# ECE411.net
KiCad netlist of a schematic drawn in EAGLE
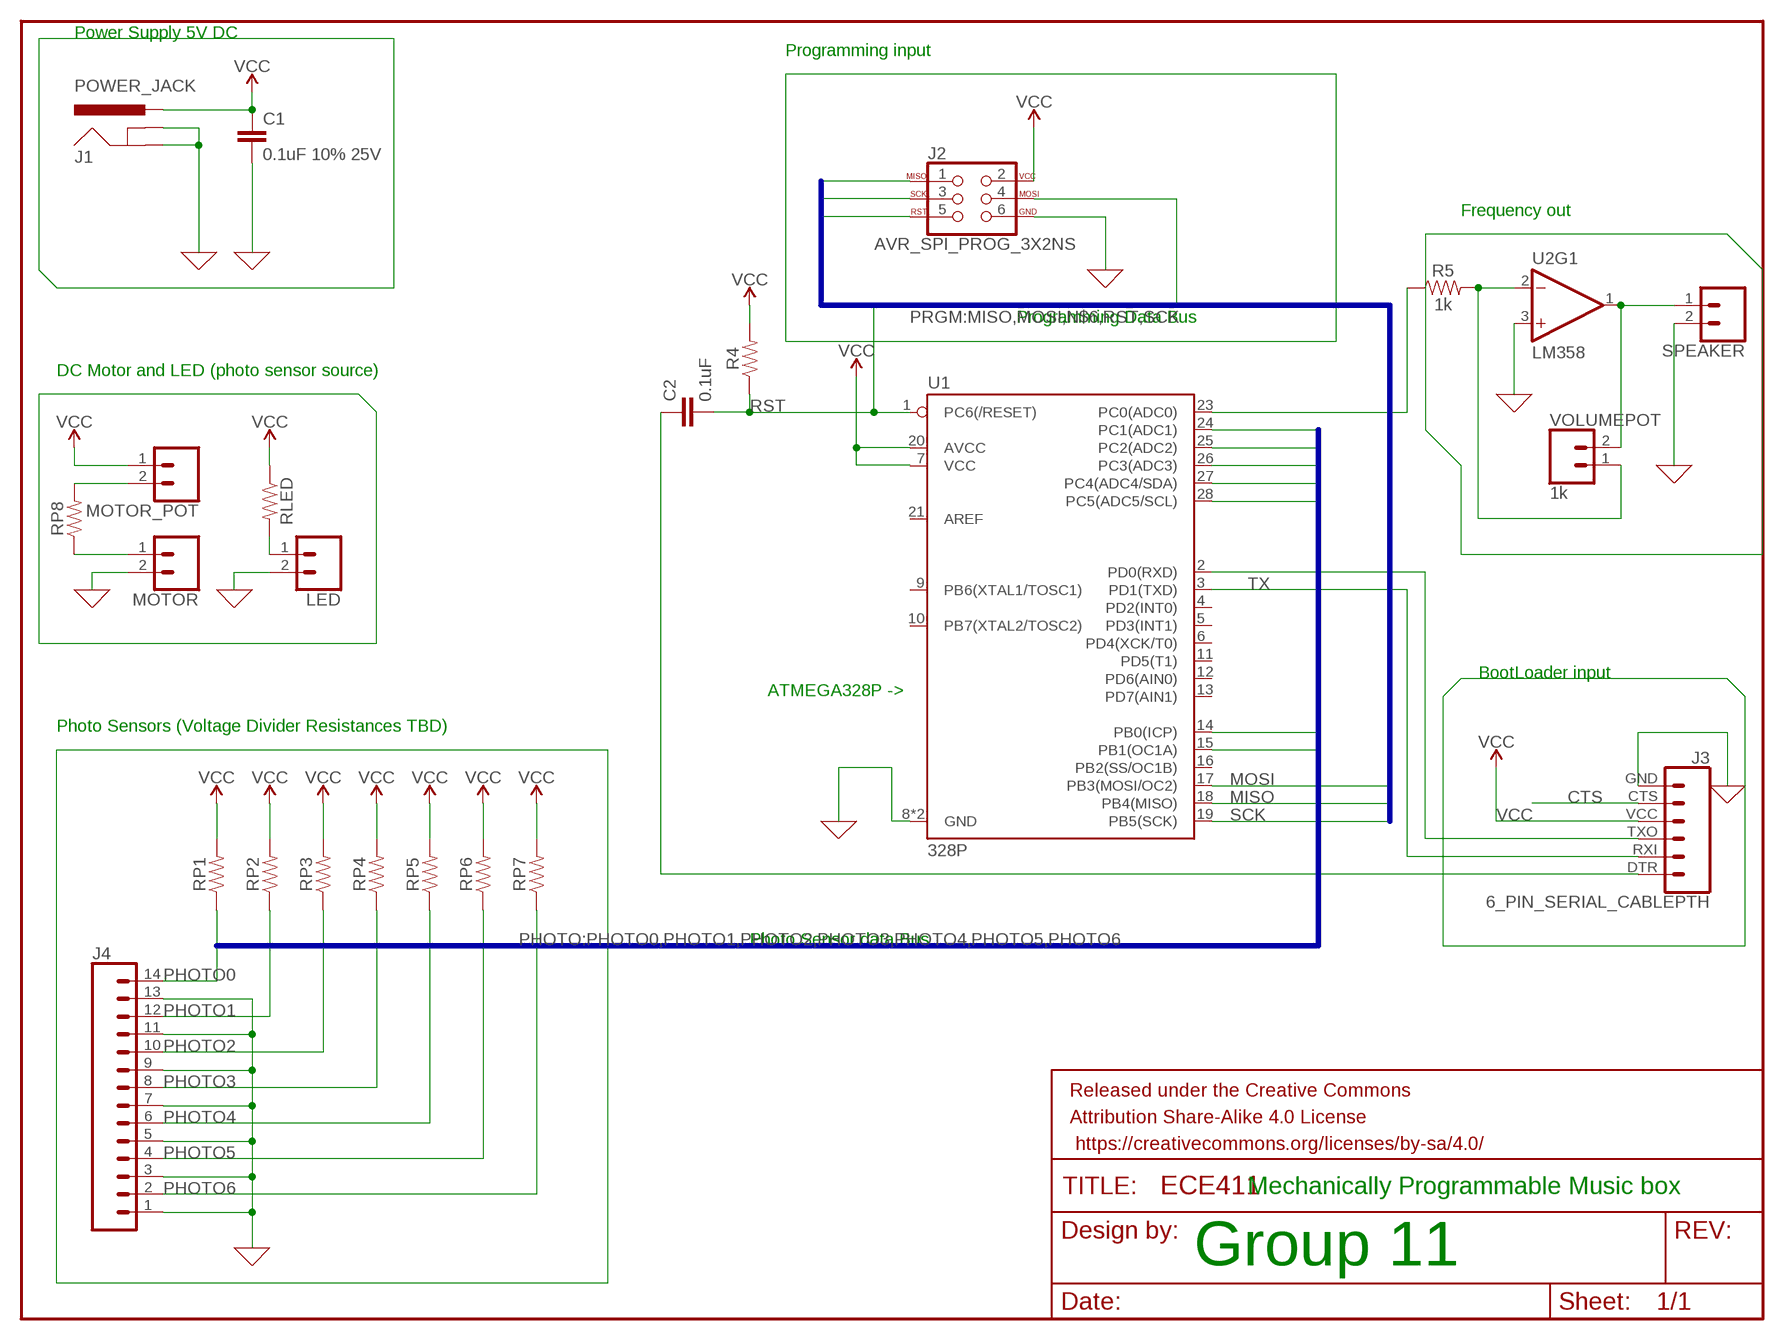
[diagram p0: schematic, sheet 1]

(export (version "E")
  (design (tool "Eeschema 10.0.6"))
  (components
    (comp (ref "C1")
      (value "0.1uF 10% 25V")
      (footprint "eagle-import:0603")
      (libsource (lib "eagle-import") (part "0.1UF-0603-25V-(+80/-20%)"))
    )
    (comp (ref "C2")
      (value "0.1uF")
      (footprint "eagle-import:0603")
      (libsource (lib "eagle-import") (part "0.1UF-0603-25V-(+80/-20%)"))
    )
    (comp (ref "FRAME1")
      (value "FRAME-LETTER")
      (footprint "eagle-import:CREATIVE_COMMONS")
      (libsource (lib "eagle-import") (part "FRAME-LETTER"))
    )
    (comp (ref "J1")
      (value "POWER_JACK")
      (footprint "eagle-import:POWER_JACK_PTH")
      (libsource (lib "eagle-import") (part "POWER_JACK"))
    )
    (comp (ref "J2")
      (value "AVR_SPI_PROG_3X2NS")
      (footprint "eagle-import:2X3-NS")
      (libsource (lib "eagle-import") (part "AVR_SPI_PROG_3X2NS"))
    )
    (comp (ref "J3")
      (value "6_PIN_SERIAL_CABLEPTH")
      (footprint "eagle-import:FTDI_BASIC")
      (libsource (lib "eagle-import") (part "6_PIN_SERIAL_CABLEPTH"))
    )
    (comp (ref "J4")
      (value "CONN_14")
      (footprint "eagle-import:1X14")
      (libsource (lib "eagle-import") (part "CONN_14"))
    )
    (comp (ref "LED")
      (value "CONN_02")
      (footprint "eagle-import:1X02")
      (libsource (lib "eagle-import") (part "CONN_02"))
    )
    (comp (ref "MOTOR")
      (value "CONN_02")
      (footprint "eagle-import:1X02")
      (libsource (lib "eagle-import") (part "CONN_02"))
    )
    (comp (ref "MOTOR_POT")
      (value "CONN_02")
      (footprint "eagle-import:1X02")
      (libsource (lib "eagle-import") (part "CONN_02"))
    )
    (comp (ref "R4")
      (value "RESISTOR0805")
      (footprint "eagle-import:0805")
      (libsource (lib "eagle-import") (part "RESISTOR0805"))
    )
    (comp (ref "R5")
      (value "1k")
      (footprint "eagle-import:0603")
      (libsource (lib "eagle-import") (part "1KOHM-0603-1/10W-1%"))
    )
    (comp (ref "RLED")
      (value "RESISTOR0603")
      (footprint "eagle-import:0603")
      (libsource (lib "eagle-import") (part "RESISTOR0603"))
    )
    (comp (ref "RP1")
      (value "RESISTOR0603")
      (footprint "eagle-import:0603")
      (libsource (lib "eagle-import") (part "RESISTOR0603"))
    )
    (comp (ref "RP2")
      (value "RESISTOR0603")
      (footprint "eagle-import:0603")
      (libsource (lib "eagle-import") (part "RESISTOR0603"))
    )
    (comp (ref "RP3")
      (value "RESISTOR0603")
      (footprint "eagle-import:0603")
      (libsource (lib "eagle-import") (part "RESISTOR0603"))
    )
    (comp (ref "RP4")
      (value "RESISTOR0603")
      (footprint "eagle-import:0603")
      (libsource (lib "eagle-import") (part "RESISTOR0603"))
    )
    (comp (ref "RP5")
      (value "RESISTOR0603")
      (footprint "eagle-import:0603")
      (libsource (lib "eagle-import") (part "RESISTOR0603"))
    )
    (comp (ref "RP6")
      (value "RESISTOR0603")
      (footprint "eagle-import:0603")
      (libsource (lib "eagle-import") (part "RESISTOR0603"))
    )
    (comp (ref "RP7")
      (value "RESISTOR0603")
      (footprint "eagle-import:0603")
      (libsource (lib "eagle-import") (part "RESISTOR0603"))
    )
    (comp (ref "RP8")
      (value "RESISTOR0603")
      (footprint "eagle-import:0603")
      (libsource (lib "eagle-import") (part "RESISTOR0603"))
    )
    (comp (ref "SPEAKER")
      (value "CONN_02")
      (footprint "eagle-import:1X02")
      (libsource (lib "eagle-import") (part "CONN_02"))
    )
    (comp (ref "U1")
      (value "328P")
      (footprint "eagle-import:DIP28")
      (libsource (lib "eagle-import") (part "ATMEGA328P_PDIP"))
    )
    (comp (ref "U2")
      (value "LM358")
      (footprint "eagle-import:DIP08")
      (libsource (lib "eagle-import") (part "LM358"))
    )
    (comp (ref "VOLUMEPOT")
      (value "1k")
      (footprint "eagle-import:1X02")
      (libsource (lib "eagle-import") (part "CONN_02"))
    )
  )
  (nets
    (net (code "4") (name "/CTS") (class "Default")
      (node (ref "J3") (pin "CTS") (pinfunction "5_CTS") (pintype "passive"))
    )
    (net (code "5") (name "/MISO") (class "Default")
      (node (ref "J2") (pin "1") (pinfunction "1_1") (pintype "passive"))
      (node (ref "U1") (pin "18") (pinfunction "PB4(MISO)_18") (pintype "bidirectional"))
    )
    (net (code "6") (name "/MOSI") (class "Default")
      (node (ref "J2") (pin "4") (pinfunction "4_4") (pintype "passive"))
      (node (ref "U1") (pin "17") (pinfunction "PB3(MOSI/OC2)_17") (pintype "bidirectional"))
    )
    (net (code "7") (name "/PHOTO0") (class "Default")
      (node (ref "J4") (pin "14") (pinfunction "14_14") (pintype "passive"))
      (node (ref "RP1") (pin "1") (pinfunction "1_1") (pintype "passive"))
      (node (ref "U1") (pin "24") (pinfunction "PC1(ADC1)_24") (pintype "bidirectional"))
    )
    (net (code "8") (name "/PHOTO1") (class "Default")
      (node (ref "J4") (pin "12") (pinfunction "12_12") (pintype "passive"))
      (node (ref "RP2") (pin "1") (pinfunction "1_1") (pintype "passive"))
      (node (ref "U1") (pin "25") (pinfunction "PC2(ADC2)_25") (pintype "bidirectional"))
    )
    (net (code "9") (name "/PHOTO2") (class "Default")
      (node (ref "J4") (pin "10") (pinfunction "10_10") (pintype "passive"))
      (node (ref "RP3") (pin "1") (pinfunction "1_1") (pintype "passive"))
      (node (ref "U1") (pin "26") (pinfunction "PC3(ADC3)_26") (pintype "bidirectional"))
    )
    (net (code "10") (name "/PHOTO3") (class "Default")
      (node (ref "J4") (pin "8") (pinfunction "8_8") (pintype "passive"))
      (node (ref "RP4") (pin "1") (pinfunction "1_1") (pintype "passive"))
      (node (ref "U1") (pin "27") (pinfunction "PC4(ADC4/SDA)_27") (pintype "bidirectional"))
    )
    (net (code "11") (name "/PHOTO4") (class "Default")
      (node (ref "J4") (pin "6") (pinfunction "6_6") (pintype "passive"))
      (node (ref "RP5") (pin "1") (pinfunction "1_1") (pintype "passive"))
      (node (ref "U1") (pin "28") (pinfunction "PC5(ADC5/SCL)_28") (pintype "bidirectional"))
    )
    (net (code "12") (name "/PHOTO5") (class "Default")
      (node (ref "J4") (pin "4") (pinfunction "4_4") (pintype "passive"))
      (node (ref "RP6") (pin "1") (pinfunction "1_1") (pintype "passive"))
      (node (ref "U1") (pin "14") (pinfunction "PB0(ICP)_14") (pintype "bidirectional"))
    )
    (net (code "13") (name "/PHOTO6") (class "Default")
      (node (ref "J4") (pin "2") (pinfunction "2_2") (pintype "passive"))
      (node (ref "RP7") (pin "1") (pinfunction "1_1") (pintype "passive"))
      (node (ref "U1") (pin "15") (pinfunction "PB1(OC1A)_15") (pintype "bidirectional"))
    )
    (net (code "14") (name "/RST") (class "Default")
      (node (ref "C2") (pin "2") (pinfunction "2_2") (pintype "passive"))
      (node (ref "J2") (pin "5") (pinfunction "5_5") (pintype "passive"))
      (node (ref "R4") (pin "1") (pinfunction "1_1") (pintype "passive"))
      (node (ref "U1") (pin "1") (pinfunction "PC6(/RESET)_1") (pintype "bidirectional"))
    )
    (net (code "15") (name "/SCK") (class "Default")
      (node (ref "J2") (pin "3") (pinfunction "3_3") (pintype "passive"))
      (node (ref "U1") (pin "19") (pinfunction "PB5(SCK)_19") (pintype "bidirectional"))
    )
    (net (code "16") (name "/TX") (class "Default")
      (node (ref "J3") (pin "RXI") (pinfunction "2_RXI") (pintype "passive"))
      (node (ref "U1") (pin "3") (pinfunction "PD1(TXD)_3") (pintype "bidirectional"))
    )
    (net (code "19") (name "GND") (class "Default")
      (node (ref "C1") (pin "2") (pinfunction "2_2") (pintype "passive"))
      (node (ref "J1") (pin "GND") (pinfunction "GND_GND") (pintype "bidirectional"))
      (node (ref "J1") (pin "GNDBREAK") (pinfunction "GNDBREAK_GNDBREAK") (pintype "bidirectional"))
      (node (ref "J2") (pin "6") (pinfunction "6_6") (pintype "passive"))
      (node (ref "J3") (pin "GND") (pinfunction "6_GND") (pintype "passive"))
      (node (ref "J4") (pin "1") (pinfunction "1_1") (pintype "passive"))
      (node (ref "J4") (pin "11") (pinfunction "11_11") (pintype "passive"))
      (node (ref "J4") (pin "13") (pinfunction "13_13") (pintype "passive"))
      (node (ref "J4") (pin "3") (pinfunction "3_3") (pintype "passive"))
      (node (ref "J4") (pin "5") (pinfunction "5_5") (pintype "passive"))
      (node (ref "J4") (pin "7") (pinfunction "7_7") (pintype "passive"))
      (node (ref "J4") (pin "9") (pinfunction "9_9") (pintype "passive"))
      (node (ref "LED") (pin "2") (pinfunction "2_2") (pintype "passive"))
      (node (ref "MOTOR") (pin "2") (pinfunction "2_2") (pintype "passive"))
      (node (ref "SPEAKER") (pin "2") (pinfunction "2_2") (pintype "passive"))
      (node (ref "U1") (pin "22") (pinfunction "GND_22") (pintype "bidirectional"))
      (node (ref "U1") (pin "8") (pinfunction "GND_8") (pintype "bidirectional"))
      (node (ref "U2") (pin "3") (pinfunction "+IN_3") (pintype "input"))
    )
    (net (code "20") (name "Net-(J3-1)") (class "Default")
      (node (ref "C2") (pin "1") (pinfunction "1_1") (pintype "passive"))
      (node (ref "J3") (pin "DTR") (pinfunction "1_DTR") (pintype "passive"))
    )
    (net (code "21") (name "Net-(J3-3)") (class "Default")
      (node (ref "J3") (pin "TXO") (pinfunction "3_TXO") (pintype "passive"))
      (node (ref "U1") (pin "2") (pinfunction "PD0(RXD)_2") (pintype "bidirectional"))
    )
    (net (code "22") (name "Net-(LED-Pad1)") (class "Default")
      (node (ref "LED") (pin "1") (pinfunction "1_1") (pintype "passive"))
      (node (ref "RLED") (pin "2") (pinfunction "2_2") (pintype "passive"))
    )
    (net (code "23") (name "Net-(MOTOR-Pad1)") (class "Default")
      (node (ref "MOTOR") (pin "1") (pinfunction "1_1") (pintype "passive"))
      (node (ref "RP8") (pin "1") (pinfunction "1_1") (pintype "passive"))
    )
    (net (code "24") (name "Net-(MOTOR_POT-Pad2)") (class "Default")
      (node (ref "MOTOR_POT") (pin "2") (pinfunction "2_2") (pintype "passive"))
      (node (ref "RP8") (pin "2") (pinfunction "2_2") (pintype "passive"))
    )
    (net (code "25") (name "Net-(U1-PC0(ADC0))") (class "Default")
      (node (ref "R5") (pin "1") (pinfunction "1_1") (pintype "passive"))
      (node (ref "U1") (pin "23") (pinfunction "PC0(ADC0)_23") (pintype "bidirectional"))
    )
    (net (code "26") (name "Net-(U2A--IN)") (class "Default")
      (node (ref "R5") (pin "2") (pinfunction "2_2") (pintype "passive"))
      (node (ref "U2") (pin "2") (pinfunction "-IN_2") (pintype "input"))
      (node (ref "VOLUMEPOT") (pin "1") (pinfunction "1_1") (pintype "passive"))
    )
    (net (code "27") (name "Net-(U2A-OUT)") (class "Default")
      (node (ref "SPEAKER") (pin "1") (pinfunction "1_1") (pintype "passive"))
      (node (ref "U2") (pin "1") (pinfunction "OUT_1") (pintype "output"))
      (node (ref "VOLUMEPOT") (pin "2") (pinfunction "2_2") (pintype "passive"))
    )
    (net (code "28") (name "VCC") (class "Default")
      (node (ref "C1") (pin "1") (pinfunction "1_1") (pintype "passive"))
      (node (ref "J1") (pin "PWR") (pinfunction "PWR_PWR") (pintype "bidirectional"))
      (node (ref "J2") (pin "2") (pinfunction "2_2") (pintype "passive"))
      (node (ref "J3") (pin "VCC") (pinfunction "4_VCC") (pintype "passive"))
      (node (ref "MOTOR_POT") (pin "1") (pinfunction "1_1") (pintype "passive"))
      (node (ref "R4") (pin "2") (pinfunction "2_2") (pintype "passive"))
      (node (ref "RLED") (pin "1") (pinfunction "1_1") (pintype "passive"))
      (node (ref "RP1") (pin "2") (pinfunction "2_2") (pintype "passive"))
      (node (ref "RP2") (pin "2") (pinfunction "2_2") (pintype "passive"))
      (node (ref "RP3") (pin "2") (pinfunction "2_2") (pintype "passive"))
      (node (ref "RP4") (pin "2") (pinfunction "2_2") (pintype "passive"))
      (node (ref "RP5") (pin "2") (pinfunction "2_2") (pintype "passive"))
      (node (ref "RP6") (pin "2") (pinfunction "2_2") (pintype "passive"))
      (node (ref "RP7") (pin "2") (pinfunction "2_2") (pintype "passive"))
      (node (ref "U1") (pin "20") (pinfunction "AVCC_20") (pintype "bidirectional"))
      (node (ref "U1") (pin "7") (pinfunction "VCC_7") (pintype "bidirectional"))
    )
    (net (code "29") (name "unconnected-(U1-AREF-Pad21)") (class "Default")
      (node (ref "U1") (pin "21") (pinfunction "AREF_21") (pintype "bidirectional"))
    )
    (net (code "30") (name "unconnected-(U1-PB2(SS{slash}OC1B)-Pad16)") (class "Default")
      (node (ref "U1") (pin "16") (pinfunction "PB2(SS/OC1B)_16") (pintype "bidirectional"))
    )
    (net (code "31") (name "unconnected-(U1-PB6(XTAL1{slash}TOSC1)-Pad9)") (class "Default")
      (node (ref "U1") (pin "9") (pinfunction "PB6(XTAL1/TOSC1)_9") (pintype "bidirectional"))
    )
    (net (code "32") (name "unconnected-(U1-PB7(XTAL2{slash}TOSC2)-Pad10)") (class "Default")
      (node (ref "U1") (pin "10") (pinfunction "PB7(XTAL2/TOSC2)_10") (pintype "bidirectional"))
    )
    (net (code "33") (name "unconnected-(U1-PD2(INT0)-Pad4)") (class "Default")
      (node (ref "U1") (pin "4") (pinfunction "PD2(INT0)_4") (pintype "bidirectional"))
    )
    (net (code "34") (name "unconnected-(U1-PD3(INT1)-Pad5)") (class "Default")
      (node (ref "U1") (pin "5") (pinfunction "PD3(INT1)_5") (pintype "bidirectional"))
    )
    (net (code "35") (name "unconnected-(U1-PD4(XCK{slash}T0)-Pad6)") (class "Default")
      (node (ref "U1") (pin "6") (pinfunction "PD4(XCK/T0)_6") (pintype "bidirectional"))
    )
    (net (code "36") (name "unconnected-(U1-PD5(T1)-Pad11)") (class "Default")
      (node (ref "U1") (pin "11") (pinfunction "PD5(T1)_11") (pintype "bidirectional"))
    )
    (net (code "37") (name "unconnected-(U1-PD6(AIN0)-Pad12)") (class "Default")
      (node (ref "U1") (pin "12") (pinfunction "PD6(AIN0)_12") (pintype "bidirectional"))
    )
    (net (code "38") (name "unconnected-(U1-PD7(AIN1)-Pad13)") (class "Default")
      (node (ref "U1") (pin "13") (pinfunction "PD7(AIN1)_13") (pintype "bidirectional"))
    )
  )
)
